# SWITCHING.net
KiCad netlist of a schematic drawn in Altium Designer
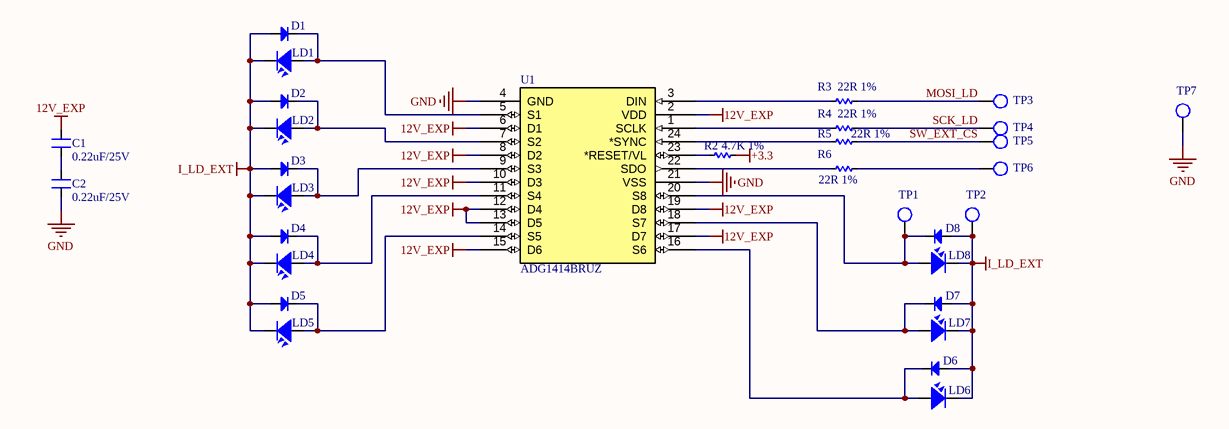
[diagram p0: SWITCHING.SchDoc]

(export (version "E")
  (design (tool "Eeschema 10.0.6"))
  (components
    (comp (ref "C1")
      (value "0.22uF/25V")
      (footprint "CN-SMD-0603")
      (description "CAP CER 0.22UF 25V X7R 0603")
      (libsource (lib "Library") (part "CN"))
    )
    (comp (ref "C2")
      (value "0.22uF/25V")
      (footprint "CN-SMD-0603")
      (description "CAP CER 0.22UF 25V X7R 0603")
      (libsource (lib "Library") (part "CN"))
    )
    (comp (ref "D1")
      (value "1N4148W-TP")
      (footprint "SOD123")
      (description "DIODE STANDARD 100V 150MA SOD123")
      (fields (field (name "PUBLISHER") "Altium Limited"))
      (libsource (lib "Library") (part "Diode SMD"))
    )
    (comp (ref "D2")
      (value "1N4148W-TP")
      (footprint "SOD123")
      (description "DIODE STANDARD 100V 150MA SOD123")
      (fields (field (name "PUBLISHER") "Altium Limited"))
      (libsource (lib "Library") (part "Diode SMD"))
    )
    (comp (ref "D3")
      (value "1N4148W-TP")
      (footprint "SOD123")
      (description "DIODE STANDARD 100V 150MA SOD123")
      (fields (field (name "PUBLISHER") "Altium Limited"))
      (libsource (lib "Library") (part "Diode SMD"))
    )
    (comp (ref "D4")
      (value "1N4148W-TP")
      (footprint "SOD123")
      (description "DIODE STANDARD 100V 150MA SOD123")
      (fields (field (name "PUBLISHER") "Altium Limited"))
      (libsource (lib "Library") (part "Diode SMD"))
    )
    (comp (ref "D5")
      (value "1N4148W-TP")
      (footprint "SOD123")
      (description "DIODE STANDARD 100V 150MA SOD123")
      (fields (field (name "PUBLISHER") "Altium Limited"))
      (libsource (lib "Library") (part "Diode SMD"))
    )
    (comp (ref "D6")
      (value "1N4148W-TP")
      (footprint "SOD123")
      (description "DIODE STANDARD 100V 150MA SOD123")
      (fields (field (name "PUBLISHER") "Altium Limited"))
      (libsource (lib "Library") (part "Diode SMD"))
    )
    (comp (ref "D7")
      (value "1N4148W-TP")
      (footprint "SOD123")
      (description "DIODE STANDARD 100V 150MA SOD123")
      (fields (field (name "PUBLISHER") "Altium Limited"))
      (libsource (lib "Library") (part "Diode SMD"))
    )
    (comp (ref "D8")
      (value "1N4148W-TP")
      (footprint "SOD123")
      (description "DIODE STANDARD 100V 150MA SOD123")
      (fields (field (name "PUBLISHER") "Altium Limited"))
      (libsource (lib "Library") (part "Diode SMD"))
    )
    (comp (ref "LD1")
      (value "LaserDiode")
      (footprint "LASER_SOCKET")
      (libsource (lib "Library") (part "LASER"))
    )
    (comp (ref "LD2")
      (value "LaserDiode")
      (footprint "LASER_SOCKET")
      (libsource (lib "Library") (part "LASER"))
    )
    (comp (ref "LD3")
      (value "LaserDiode")
      (footprint "LASER_SOCKET")
      (libsource (lib "Library") (part "LASER"))
    )
    (comp (ref "LD4")
      (value "LaserDiode")
      (footprint "LASER_SOCKET")
      (libsource (lib "Library") (part "LASER"))
    )
    (comp (ref "LD5")
      (value "LaserDiode")
      (footprint "LASER_SOCKET")
      (libsource (lib "Library") (part "LASER"))
    )
    (comp (ref "LD6")
      (value "LaserDiode")
      (footprint "LASER_SOCKET")
      (libsource (lib "Library") (part "LASER"))
    )
    (comp (ref "LD7")
      (value "LaserDiode")
      (footprint "LASER_SOCKET")
      (libsource (lib "Library") (part "LASER"))
    )
    (comp (ref "LD8")
      (value "LaserDiode")
      (footprint "LASER_SOCKET")
      (libsource (lib "Library") (part "LASER"))
    )
    (comp (ref "R2")
      (value "4.7K 1%")
      (footprint "RES-SMD-0603")
      (description "RES SMD 4.7K OHM 1% 1/10W 0603")
      (fields
        (field (name "MANUFACTURER") "Generic Components")
        (field (name "PUBLISHER") "Altium Hobart Technology Centre")
      )
      (libsource (lib "Library") (part "Res-SMD"))
    )
    (comp (ref "R3")
      (value "22R 1%")
      (footprint "RES-SMD-0603")
      (description "Resistor")
      (fields
        (field (name "MANUFACTURER") "Generic Components")
        (field (name "PUBLISHER") "Altium Hobart Technology Centre")
      )
      (libsource (lib "Library") (part "Res-SMD"))
    )
    (comp (ref "R4")
      (value "22R 1%")
      (footprint "RES-SMD-0603")
      (description "Resistor")
      (fields
        (field (name "MANUFACTURER") "Generic Components")
        (field (name "PUBLISHER") "Altium Hobart Technology Centre")
      )
      (libsource (lib "Library") (part "Res-SMD"))
    )
    (comp (ref "R5")
      (value "22R 1%")
      (footprint "RES-SMD-0603")
      (description "Resistor")
      (fields
        (field (name "MANUFACTURER") "Generic Components")
        (field (name "PUBLISHER") "Altium Hobart Technology Centre")
      )
      (libsource (lib "Library") (part "Res-SMD"))
    )
    (comp (ref "R6")
      (value "22R 1%")
      (footprint "RES-SMD-0603")
      (description "Resistor")
      (fields
        (field (name "MANUFACTURER") "Generic Components")
        (field (name "PUBLISHER") "Altium Hobart Technology Centre")
      )
      (libsource (lib "Library") (part "Res-SMD"))
    )
    (comp (ref "TP1")
      (value "Test-Point")
      (footprint "TESTPOINT")
      (libsource (lib "Library") (part "Test-Point"))
    )
    (comp (ref "TP2")
      (value "Test-Point")
      (footprint "TESTPOINT")
      (libsource (lib "Library") (part "Test-Point"))
    )
    (comp (ref "TP3")
      (value "Test-Point")
      (footprint "TESTPOINT")
      (libsource (lib "Library") (part "Test-Point"))
    )
    (comp (ref "TP4")
      (value "Test-Point")
      (footprint "TESTPOINT")
      (libsource (lib "Library") (part "Test-Point"))
    )
    (comp (ref "TP5")
      (value "Test-Point")
      (footprint "TESTPOINT")
      (libsource (lib "Library") (part "Test-Point"))
    )
    (comp (ref "TP6")
      (value "Test-Point")
      (footprint "TESTPOINT")
      (libsource (lib "Library") (part "Test-Point"))
    )
    (comp (ref "TP7")
      (value "Test-Point")
      (footprint "TESTPOINT")
      (libsource (lib "Library") (part "Test-Point"))
    )
    (comp (ref "U1")
      (value "ADG1414BRUZ")
      (footprint "TSSOP24")
      (description "IC SW SPST-NOX8 11.5OHM 24TSSOP")
      (libsource (lib "Library_HUNG") (part "ADG1414BRUZ"))
    )
  )
  (nets
    (net (code "1") (name "+3.3") (class "Default")
      (node (ref "R2") (pin "1") (pinfunction "1_1") (pintype "passive"))
    )
    (net (code "2") (name "/MOSI_LD") (class "Default")
      (node (ref "R3") (pin "1") (pinfunction "1_1") (pintype "passive"))
      (node (ref "TP3") (pin "1") (pinfunction "1_1") (pintype "passive"))
    )
    (net (code "3") (name "/SCK_LD") (class "Default")
      (node (ref "R4") (pin "1") (pinfunction "1_1") (pintype "passive"))
      (node (ref "TP4") (pin "1") (pinfunction "1_1") (pintype "passive"))
    )
    (net (code "4") (name "/SW_EXT_CS") (class "Default")
      (node (ref "R5") (pin "1") (pinfunction "1_1") (pintype "passive"))
      (node (ref "TP5") (pin "1") (pinfunction "1_1") (pintype "passive"))
    )
    (net (code "5") (name "12V_EXP") (class "Default")
      (node (ref "C1") (pin "2") (pinfunction "2_2") (pintype "passive"))
      (node (ref "U1") (pin "10") (pinfunction "D3_10") (pintype "bidirectional"))
      (node (ref "U1") (pin "12") (pinfunction "D4_12") (pintype "bidirectional"))
      (node (ref "U1") (pin "13") (pinfunction "D5_13") (pintype "bidirectional"))
      (node (ref "U1") (pin "15") (pinfunction "D6_15") (pintype "bidirectional"))
      (node (ref "U1") (pin "17") (pinfunction "D7_17") (pintype "bidirectional"))
      (node (ref "U1") (pin "19") (pinfunction "D8_19") (pintype "bidirectional"))
      (node (ref "U1") (pin "2") (pinfunction "VDD_2") (pintype "power_in"))
      (node (ref "U1") (pin "6") (pinfunction "D1_6") (pintype "bidirectional"))
      (node (ref "U1") (pin "8") (pinfunction "D2_8") (pintype "bidirectional"))
    )
    (net (code "6") (name "GND") (class "Default")
      (node (ref "C2") (pin "1") (pinfunction "1_1") (pintype "passive"))
      (node (ref "TP7") (pin "1") (pinfunction "1_1") (pintype "passive"))
      (node (ref "U1") (pin "21") (pinfunction "VSS_21") (pintype "power_in"))
      (node (ref "U1") (pin "4") (pinfunction "GND_4") (pintype "power_in"))
    )
    (net (code "7") (name "I_LD_EXT") (class "Default")
      (node (ref "D1") (pin "1") (pinfunction "A_1") (pintype "passive"))
      (node (ref "D2") (pin "1") (pinfunction "A_1") (pintype "passive"))
      (node (ref "D3") (pin "1") (pinfunction "A_1") (pintype "passive"))
      (node (ref "D4") (pin "1") (pinfunction "A_1") (pintype "passive"))
      (node (ref "D5") (pin "1") (pinfunction "A_1") (pintype "passive"))
      (node (ref "D6") (pin "1") (pinfunction "A_1") (pintype "passive"))
      (node (ref "D7") (pin "1") (pinfunction "A_1") (pintype "passive"))
      (node (ref "D8") (pin "1") (pinfunction "A_1") (pintype "passive"))
      (node (ref "LD1") (pin "3") (pinfunction "3_3") (pintype "passive"))
      (node (ref "LD2") (pin "3") (pinfunction "3_3") (pintype "passive"))
      (node (ref "LD3") (pin "3") (pinfunction "3_3") (pintype "passive"))
      (node (ref "LD4") (pin "3") (pinfunction "3_3") (pintype "passive"))
      (node (ref "LD5") (pin "3") (pinfunction "3_3") (pintype "passive"))
      (node (ref "LD6") (pin "3") (pinfunction "3_3") (pintype "passive"))
      (node (ref "LD7") (pin "3") (pinfunction "3_3") (pintype "passive"))
      (node (ref "LD8") (pin "3") (pinfunction "3_3") (pintype "passive"))
      (node (ref "TP2") (pin "1") (pinfunction "1_1") (pintype "passive"))
    )
    (net (code "8") (name "Net-(C1-Pad1)") (class "Default")
      (node (ref "C1") (pin "1") (pinfunction "1_1") (pintype "passive"))
      (node (ref "C2") (pin "2") (pinfunction "2_2") (pintype "passive"))
    )
    (net (code "9") (name "Net-(D1-K)") (class "Default")
      (node (ref "D1") (pin "2") (pinfunction "K_2") (pintype "passive"))
      (node (ref "LD1") (pin "1") (pinfunction "1_1") (pintype "passive"))
      (node (ref "U1") (pin "5") (pinfunction "S1_5") (pintype "bidirectional"))
    )
    (net (code "10") (name "Net-(D2-K)") (class "Default")
      (node (ref "D2") (pin "2") (pinfunction "K_2") (pintype "passive"))
      (node (ref "LD2") (pin "1") (pinfunction "1_1") (pintype "passive"))
      (node (ref "U1") (pin "7") (pinfunction "S2_7") (pintype "bidirectional"))
    )
    (net (code "11") (name "Net-(D3-K)") (class "Default")
      (node (ref "D3") (pin "2") (pinfunction "K_2") (pintype "passive"))
      (node (ref "LD3") (pin "1") (pinfunction "1_1") (pintype "passive"))
      (node (ref "U1") (pin "9") (pinfunction "S3_9") (pintype "bidirectional"))
    )
    (net (code "12") (name "Net-(D4-K)") (class "Default")
      (node (ref "D4") (pin "2") (pinfunction "K_2") (pintype "passive"))
      (node (ref "LD4") (pin "1") (pinfunction "1_1") (pintype "passive"))
      (node (ref "U1") (pin "11") (pinfunction "S4_11") (pintype "bidirectional"))
    )
    (net (code "13") (name "Net-(D5-K)") (class "Default")
      (node (ref "D5") (pin "2") (pinfunction "K_2") (pintype "passive"))
      (node (ref "LD5") (pin "1") (pinfunction "1_1") (pintype "passive"))
      (node (ref "U1") (pin "14") (pinfunction "S5_14") (pintype "bidirectional"))
    )
    (net (code "14") (name "Net-(D6-K)") (class "Default")
      (node (ref "D6") (pin "2") (pinfunction "K_2") (pintype "passive"))
      (node (ref "LD6") (pin "1") (pinfunction "1_1") (pintype "passive"))
      (node (ref "U1") (pin "16") (pinfunction "S6_16") (pintype "bidirectional"))
    )
    (net (code "15") (name "Net-(D7-K)") (class "Default")
      (node (ref "D7") (pin "2") (pinfunction "K_2") (pintype "passive"))
      (node (ref "LD7") (pin "1") (pinfunction "1_1") (pintype "passive"))
      (node (ref "U1") (pin "18") (pinfunction "S7_18") (pintype "bidirectional"))
    )
    (net (code "16") (name "Net-(D8-K)") (class "Default")
      (node (ref "D8") (pin "2") (pinfunction "K_2") (pintype "passive"))
      (node (ref "LD8") (pin "1") (pinfunction "1_1") (pintype "passive"))
      (node (ref "TP1") (pin "1") (pinfunction "1_1") (pintype "passive"))
      (node (ref "U1") (pin "20") (pinfunction "S8_20") (pintype "bidirectional"))
    )
    (net (code "17") (name "Net-(R6-Pad1)") (class "Default")
      (node (ref "R6") (pin "1") (pinfunction "1_1") (pintype "passive"))
      (node (ref "TP6") (pin "1") (pinfunction "1_1") (pintype "passive"))
    )
    (net (code "18") (name "Net-(U1-*RESET{slash}VL)") (class "Default")
      (node (ref "R2") (pin "2") (pinfunction "2_2") (pintype "passive"))
      (node (ref "U1") (pin "23") (pinfunction "*RESET/VL_23") (pintype "bidirectional"))
    )
    (net (code "19") (name "Net-(U1-*SYNC)") (class "Default")
      (node (ref "R5") (pin "2") (pinfunction "2_2") (pintype "passive"))
      (node (ref "U1") (pin "24") (pinfunction "*SYNC_24") (pintype "input"))
    )
    (net (code "20") (name "Net-(U1-DIN)") (class "Default")
      (node (ref "R3") (pin "2") (pinfunction "2_2") (pintype "passive"))
      (node (ref "U1") (pin "3") (pinfunction "DIN_3") (pintype "input"))
    )
    (net (code "21") (name "Net-(U1-SCLK)") (class "Default")
      (node (ref "R4") (pin "2") (pinfunction "2_2") (pintype "passive"))
      (node (ref "U1") (pin "1") (pinfunction "SCLK_1") (pintype "input"))
    )
    (net (code "22") (name "Net-(U1-SDO)") (class "Default")
      (node (ref "R6") (pin "2") (pinfunction "2_2") (pintype "passive"))
      (node (ref "U1") (pin "22") (pinfunction "SDO_22") (pintype "output"))
    )
  )
)
